# old_motor_line.net
KiCad netlist of a schematic drawn in EAGLE
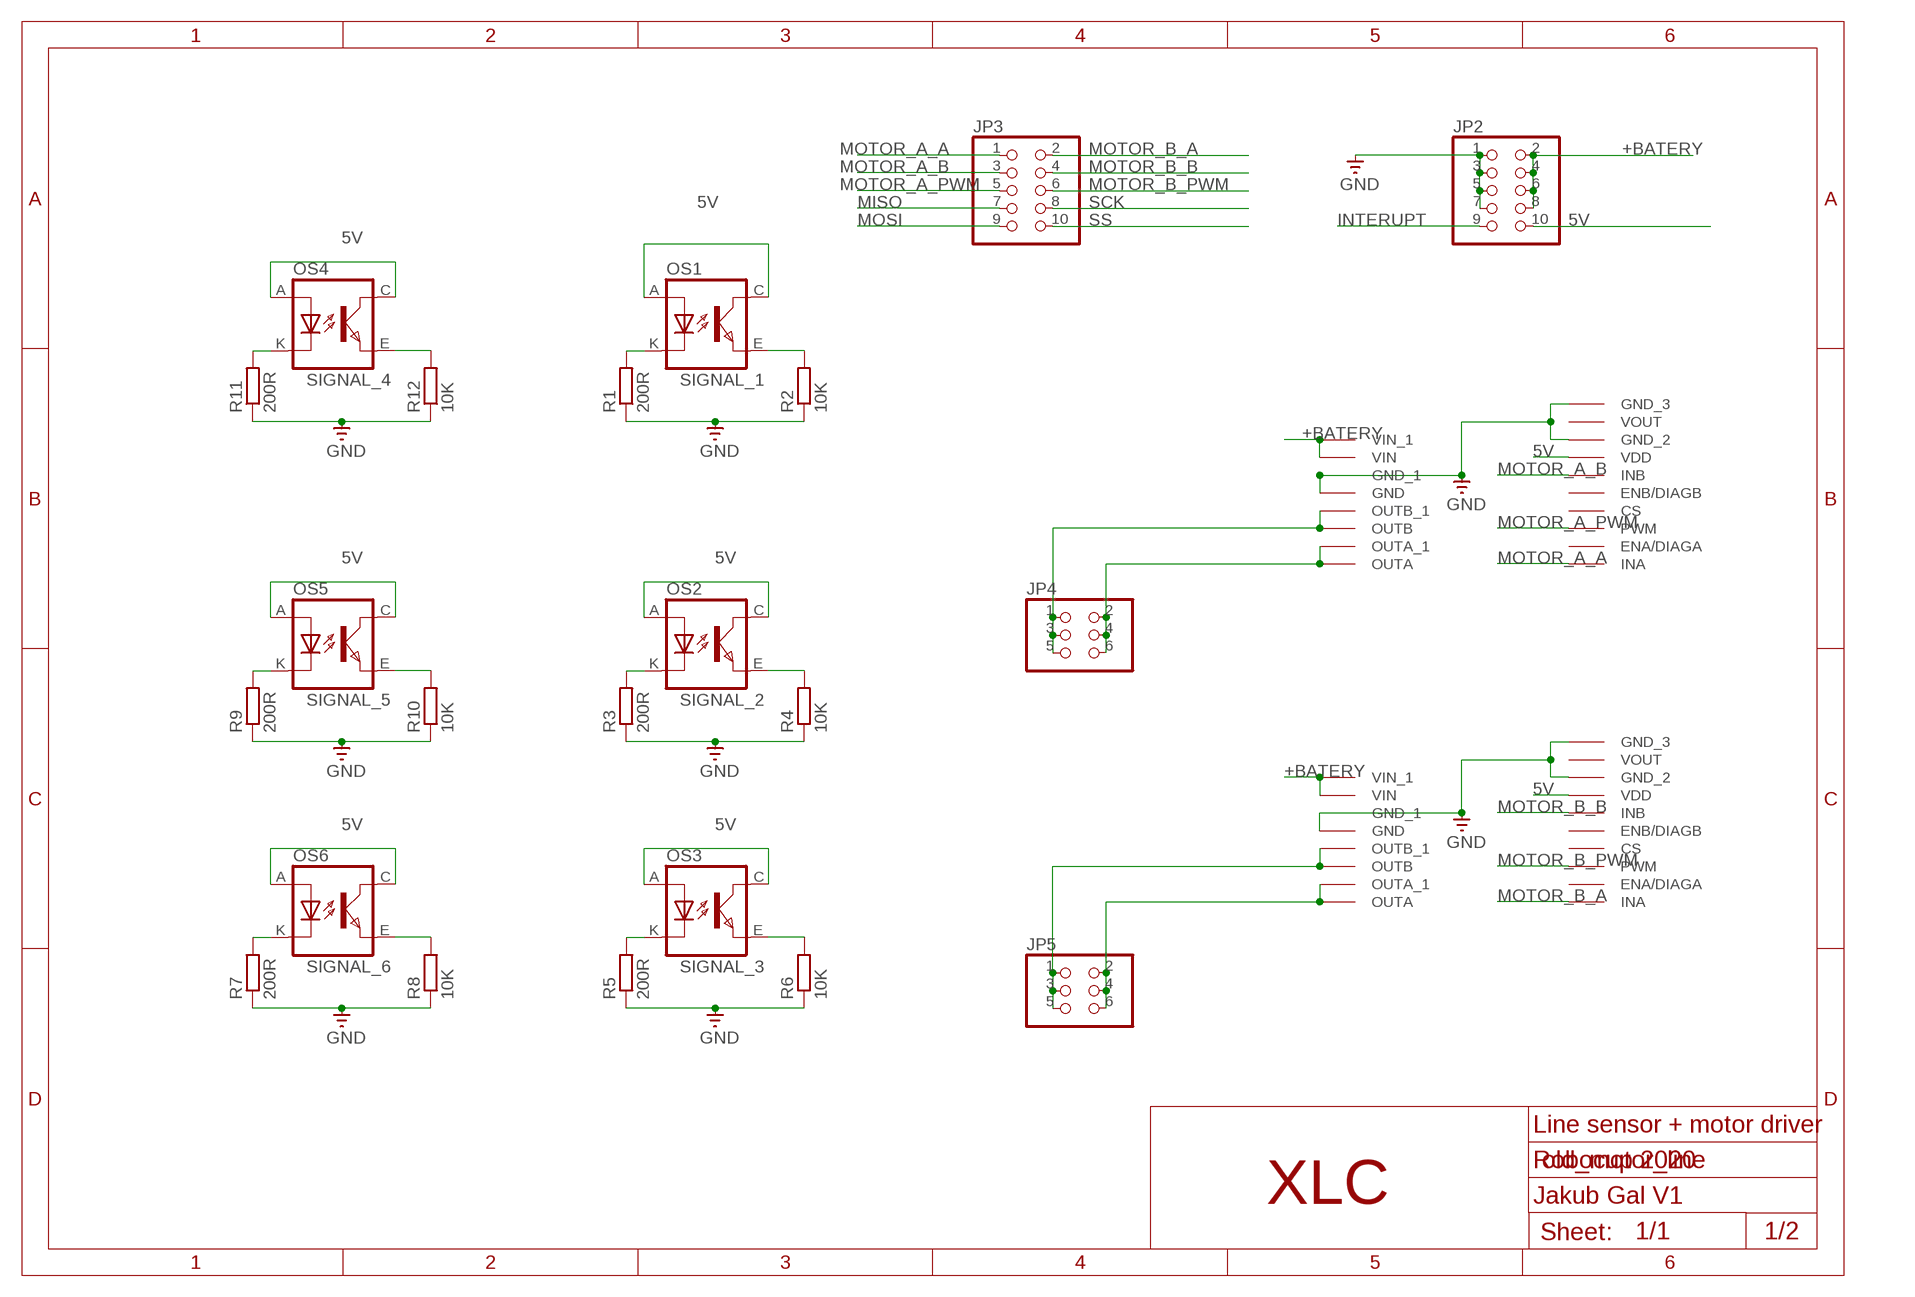
[diagram p0: schematic, sheet 1, part 1 of 2]
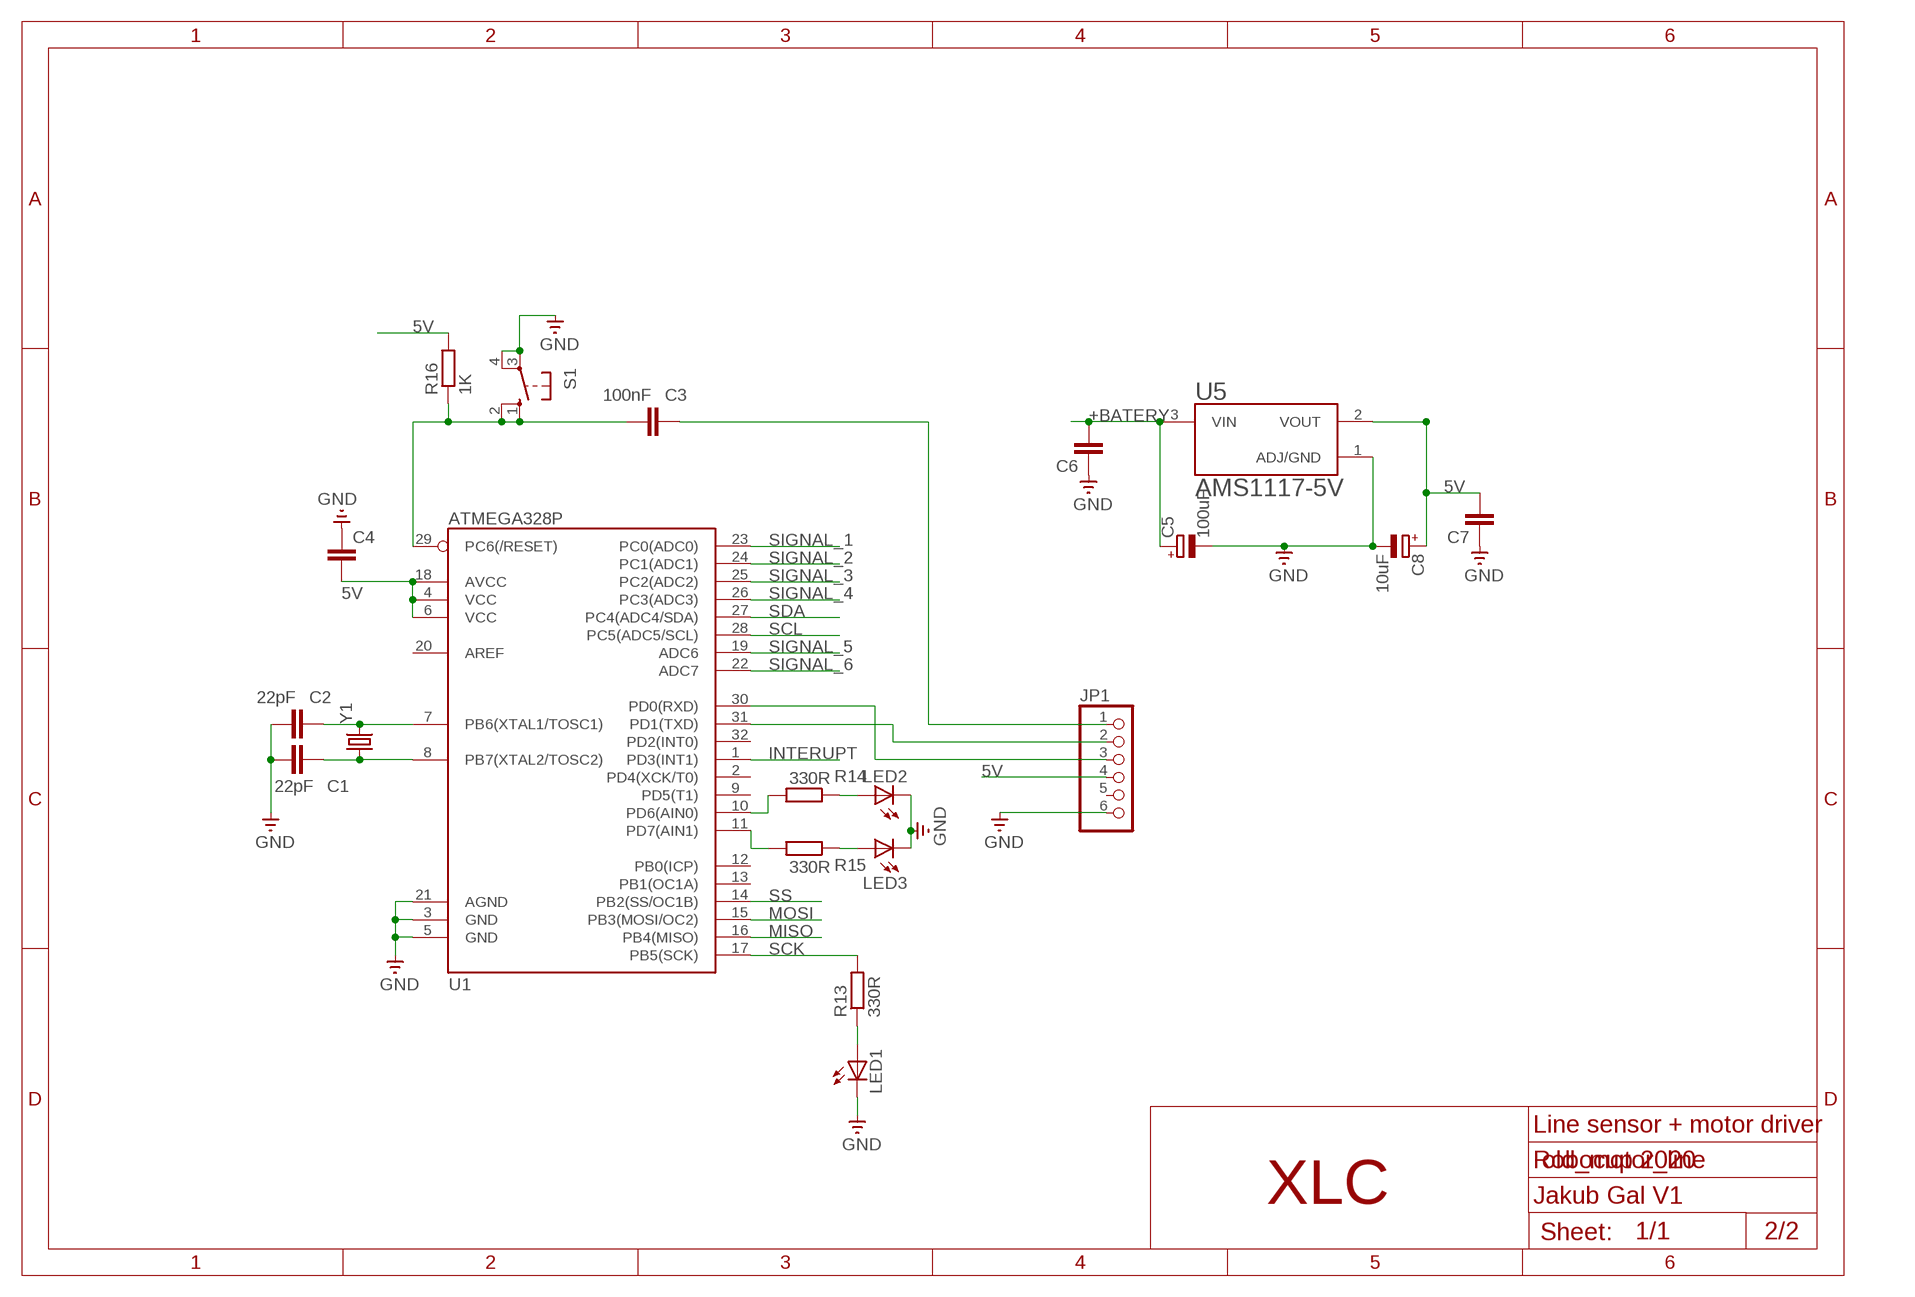
[diagram p1: schematic, sheet 1, part 2 of 2]

(export (version "E")
  (design (tool "Eeschema 10.0.6"))
  (components
    (comp (ref "C1")
      (value "22pF")
      (footprint "eagle-import:C0603")
      (libsource (lib "eagle-import") (part "rcl@1_C-EUC0603"))
    )
    (comp (ref "C2")
      (value "22pF")
      (footprint "eagle-import:C0603")
      (libsource (lib "eagle-import") (part "rcl@1_C-EUC0603"))
    )
    (comp (ref "C3")
      (value "100nF")
      (footprint "eagle-import:C0603")
      (libsource (lib "eagle-import") (part "rcl@1_C-EUC0603"))
    )
    (comp (ref "C4")
      (value "C-EUC0603")
      (footprint "eagle-import:C0603")
      (libsource (lib "eagle-import") (part "C-EUC0603"))
    )
    (comp (ref "C5")
      (value "100uF")
      (footprint "eagle-import:UD-6,3X7,7_NICHICON")
      (libsource (lib "eagle-import") (part "CPOL-EUUD-6,3X7,7"))
    )
    (comp (ref "C6")
      (value "C-EUC0603")
      (footprint "eagle-import:C0603")
      (libsource (lib "eagle-import") (part "C-EUC0603"))
    )
    (comp (ref "C7")
      (value "C-EUC0603")
      (footprint "eagle-import:C0603")
      (libsource (lib "eagle-import") (part "C-EUC0603"))
    )
    (comp (ref "C8")
      (value "10uF")
      (footprint "eagle-import:UD-4X5,8_NICHICON")
      (libsource (lib "eagle-import") (part "CPOL-EUUD-4X5,8"))
    )
    (comp (ref "JP1")
      (value "PINHD-1X6/90")
      (footprint "eagle-import:1X06_90")
      (libsource (lib "eagle-import") (part "PINHD-1X6/90"))
    )
    (comp (ref "JP2")
      (value "PINHD-2X5")
      (footprint "eagle-import:2X05")
      (libsource (lib "eagle-import") (part "PINHD-2X5"))
    )
    (comp (ref "JP3")
      (value "PINHD-2X5")
      (footprint "eagle-import:2X05")
      (libsource (lib "eagle-import") (part "PINHD-2X5"))
    )
    (comp (ref "JP4")
      (value "PINHD-2X3")
      (footprint "eagle-import:2X03")
      (libsource (lib "eagle-import") (part "PINHD-2X3"))
    )
    (comp (ref "JP5")
      (value "PINHD-2X3")
      (footprint "eagle-import:2X03")
      (libsource (lib "eagle-import") (part "PINHD-2X3"))
    )
    (comp (ref "LED1")
      (value "LEDCHIPLED_0603")
      (footprint "eagle-import:CHIPLED_0603")
      (libsource (lib "eagle-import") (part "LEDCHIPLED_0603"))
    )
    (comp (ref "LED2")
      (value "LEDCHIPLED_0603")
      (footprint "eagle-import:CHIPLED_0603")
      (libsource (lib "eagle-import") (part "LEDCHIPLED_0603"))
    )
    (comp (ref "LED3")
      (value "LEDCHIPLED_0603")
      (footprint "eagle-import:CHIPLED_0603")
      (libsource (lib "eagle-import") (part "LEDCHIPLED_0603"))
    )
    (comp (ref "OS1")
      (value "TCRT5000")
      (footprint "eagle-import:TCRT5000")
      (libsource (lib "eagle-import") (part "TCRT5000"))
    )
    (comp (ref "OS2")
      (value "TCRT5000")
      (footprint "eagle-import:TCRT5000")
      (libsource (lib "eagle-import") (part "TCRT5000"))
    )
    (comp (ref "OS3")
      (value "TCRT5000")
      (footprint "eagle-import:TCRT5000")
      (libsource (lib "eagle-import") (part "TCRT5000"))
    )
    (comp (ref "OS4")
      (value "TCRT5000")
      (footprint "eagle-import:TCRT5000")
      (fields (field (name "SPICEPREFIX") "O"))
      (libsource (lib "eagle-import") (part "TCRT5000"))
    )
    (comp (ref "OS5")
      (value "TCRT5000")
      (footprint "eagle-import:TCRT5000")
      (libsource (lib "eagle-import") (part "TCRT5000"))
    )
    (comp (ref "OS6")
      (value "TCRT5000")
      (footprint "eagle-import:TCRT5000")
      (fields (field (name "SPICEPREFIX") "O"))
      (libsource (lib "eagle-import") (part "TCRT5000"))
    )
    (comp (ref "R1")
      (value "200R")
      (footprint "eagle-import:R0603")
      (libsource (lib "eagle-import") (part "R-EU_R0603"))
    )
    (comp (ref "R2")
      (value "10K")
      (footprint "eagle-import:R0603")
      (libsource (lib "eagle-import") (part "R-EU_R0603"))
    )
    (comp (ref "R3")
      (value "200R")
      (footprint "eagle-import:R0603")
      (libsource (lib "eagle-import") (part "R-EU_R0603"))
    )
    (comp (ref "R4")
      (value "10K")
      (footprint "eagle-import:R0603")
      (libsource (lib "eagle-import") (part "R-EU_R0603"))
    )
    (comp (ref "R5")
      (value "200R")
      (footprint "eagle-import:R0603")
      (libsource (lib "eagle-import") (part "R-EU_R0603"))
    )
    (comp (ref "R6")
      (value "10K")
      (footprint "eagle-import:R0603")
      (libsource (lib "eagle-import") (part "R-EU_R0603"))
    )
    (comp (ref "R7")
      (value "200R")
      (footprint "eagle-import:R0603")
      (libsource (lib "eagle-import") (part "R-EU_R0603"))
    )
    (comp (ref "R8")
      (value "10K")
      (footprint "eagle-import:R0603")
      (libsource (lib "eagle-import") (part "R-EU_R0603"))
    )
    (comp (ref "R9")
      (value "200R")
      (footprint "eagle-import:R0603")
      (libsource (lib "eagle-import") (part "R-EU_R0603"))
    )
    (comp (ref "R10")
      (value "10K")
      (footprint "eagle-import:R0603")
      (libsource (lib "eagle-import") (part "R-EU_R0603"))
    )
    (comp (ref "R11")
      (value "200R")
      (footprint "eagle-import:R0603")
      (libsource (lib "eagle-import") (part "R-EU_R0603"))
    )
    (comp (ref "R12")
      (value "10K")
      (footprint "eagle-import:R0603")
      (libsource (lib "eagle-import") (part "R-EU_R0603"))
    )
    (comp (ref "R13")
      (value "330R")
      (footprint "eagle-import:R0603")
      (libsource (lib "eagle-import") (part "R-EU_R0603"))
    )
    (comp (ref "R14")
      (value "330R")
      (footprint "eagle-import:R0603")
      (libsource (lib "eagle-import") (part "R-EU_R0603"))
    )
    (comp (ref "R15")
      (value "330R")
      (footprint "eagle-import:R0603")
      (libsource (lib "eagle-import") (part "R-EU_R0603"))
    )
    (comp (ref "R16")
      (value "1K")
      (footprint "eagle-import:R0603")
      (libsource (lib "eagle-import") (part "R-EU_R0603"))
    )
    (comp (ref "S1")
      (value "10-XX")
      (footprint "eagle-import:B3F-10XX")
      (fields (field (name "MPN") "B3F-1000"))
      (libsource (lib "eagle-import") (part "10-XX"))
    )
    (comp (ref "U$1")
      (value "MOTOR_DRIVER")
      (footprint "eagle-import:MOTOR_DRIVER")
      (libsource (lib "eagle-import") (part "MOTOR_DRIVER"))
    )
    (comp (ref "U$2")
      (value "MOTOR_DRIVER")
      (footprint "eagle-import:MOTOR_DRIVER")
      (libsource (lib "eagle-import") (part "MOTOR_DRIVER"))
    )
    (comp (ref "U1")
      (value "ATMEGA328P")
      (footprint "eagle-import:TQFP32-08")
      (libsource (lib "eagle-import") (part "ATMEGA328_SMT"))
    )
    (comp (ref "U5")
      (value "AMS1117-5V")
      (footprint "eagle-import:SOT229P700X180-4N")
      (fields (field (name "MF") "Advanced Monolithic Systems") (field (name "MP") "AMS1117-3.3"))
      (libsource (lib "eagle-import") (part "AMS1117-3.3"))
    )
    (comp (ref "Y1")
      (value "CRYSTALHC49US")
      (footprint "eagle-import:HC49US")
      (libsource (lib "eagle-import") (part "CRYSTALHC49US"))
    )
  )
  (nets
    (net (code "1") (name "/+BATERY") (class "Default")
      (node (ref "C5") (pin "+") (pinfunction "+_+") (pintype "passive"))
      (node (ref "C6") (pin "2") (pinfunction "2_2") (pintype "passive"))
      (node (ref "JP2") (pin "2") (pinfunction "2_2") (pintype "passive"))
      (node (ref "JP2") (pin "4") (pinfunction "4_4") (pintype "passive"))
      (node (ref "JP2") (pin "6") (pinfunction "6_6") (pintype "passive"))
      (node (ref "JP2") (pin "8") (pinfunction "8_8") (pintype "passive"))
      (node (ref "U$1") (pin "VIN") (pinfunction "VIN_VIN") (pintype "bidirectional"))
      (node (ref "U$1") (pin "VIN_1") (pinfunction "VIN_1_VIN_1") (pintype "bidirectional"))
      (node (ref "U$2") (pin "VIN") (pinfunction "VIN_VIN") (pintype "bidirectional"))
      (node (ref "U$2") (pin "VIN_1") (pinfunction "VIN_1_VIN_1") (pintype "bidirectional"))
      (node (ref "U5") (pin "3") (pinfunction "VIN_3") (pintype "input"))
    )
    (net (code "2") (name "/5V") (class "Default")
      (node (ref "C4") (pin "2") (pinfunction "2_2") (pintype "passive"))
      (node (ref "C7") (pin "2") (pinfunction "2_2") (pintype "passive"))
      (node (ref "C8") (pin "+") (pinfunction "+_+") (pintype "passive"))
      (node (ref "JP1") (pin "4") (pinfunction "4_4") (pintype "passive"))
      (node (ref "JP2") (pin "10") (pinfunction "10_10") (pintype "passive"))
      (node (ref "OS1") (pin "A") (pinfunction "ANODE_A") (pintype "passive"))
      (node (ref "OS1") (pin "C") (pinfunction "COLLECTOR_C") (pintype "passive"))
      (node (ref "OS2") (pin "A") (pinfunction "ANODE_A") (pintype "passive"))
      (node (ref "OS2") (pin "C") (pinfunction "COLLECTOR_C") (pintype "passive"))
      (node (ref "OS3") (pin "A") (pinfunction "ANODE_A") (pintype "passive"))
      (node (ref "OS3") (pin "C") (pinfunction "COLLECTOR_C") (pintype "passive"))
      (node (ref "OS4") (pin "A") (pinfunction "ANODE_A") (pintype "passive"))
      (node (ref "OS4") (pin "C") (pinfunction "COLLECTOR_C") (pintype "passive"))
      (node (ref "OS5") (pin "A") (pinfunction "ANODE_A") (pintype "passive"))
      (node (ref "OS5") (pin "C") (pinfunction "COLLECTOR_C") (pintype "passive"))
      (node (ref "OS6") (pin "A") (pinfunction "ANODE_A") (pintype "passive"))
      (node (ref "OS6") (pin "C") (pinfunction "COLLECTOR_C") (pintype "passive"))
      (node (ref "R16") (pin "2") (pinfunction "2_2") (pintype "passive"))
      (node (ref "U$1") (pin "VDD") (pinfunction "VDD_VDD") (pintype "bidirectional"))
      (node (ref "U$2") (pin "VDD") (pinfunction "VDD_VDD") (pintype "bidirectional"))
      (node (ref "U1") (pin "18") (pinfunction "AVCC_18") (pintype "bidirectional"))
      (node (ref "U1") (pin "4") (pinfunction "VCC_4") (pintype "bidirectional"))
      (node (ref "U1") (pin "6") (pinfunction "VCC_6") (pintype "bidirectional"))
      (node (ref "U5") (pin "2") (pinfunction "VOUT_2") (pintype "output"))
    )
    (net (code "3") (name "/INTERUPT") (class "Default")
      (node (ref "JP2") (pin "9") (pinfunction "9_9") (pintype "passive"))
      (node (ref "U1") (pin "1") (pinfunction "PD3(INT1)_1") (pintype "bidirectional"))
    )
    (net (code "4") (name "/MISO") (class "Default")
      (node (ref "JP3") (pin "7") (pinfunction "7_7") (pintype "passive"))
      (node (ref "U1") (pin "16") (pinfunction "PB4(MISO)_16") (pintype "bidirectional"))
    )
    (net (code "5") (name "/MOSI") (class "Default")
      (node (ref "JP3") (pin "9") (pinfunction "9_9") (pintype "passive"))
      (node (ref "U1") (pin "15") (pinfunction "PB3(MOSI/OC2)_15") (pintype "bidirectional"))
    )
    (net (code "6") (name "/MOTOR_A_A") (class "Default")
      (node (ref "JP3") (pin "1") (pinfunction "1_1") (pintype "passive"))
      (node (ref "U$1") (pin "INA") (pinfunction "INA_INA") (pintype "bidirectional"))
    )
    (net (code "7") (name "/MOTOR_A_B") (class "Default")
      (node (ref "JP3") (pin "3") (pinfunction "3_3") (pintype "passive"))
      (node (ref "U$1") (pin "INB") (pinfunction "INB_INB") (pintype "bidirectional"))
    )
    (net (code "8") (name "/MOTOR_A_PWM") (class "Default")
      (node (ref "JP3") (pin "5") (pinfunction "5_5") (pintype "passive"))
      (node (ref "U$1") (pin "PWM") (pinfunction "PWM_PWM") (pintype "bidirectional"))
    )
    (net (code "9") (name "/MOTOR_B_A") (class "Default")
      (node (ref "JP3") (pin "2") (pinfunction "2_2") (pintype "passive"))
      (node (ref "U$2") (pin "INA") (pinfunction "INA_INA") (pintype "bidirectional"))
    )
    (net (code "10") (name "/MOTOR_B_B") (class "Default")
      (node (ref "JP3") (pin "4") (pinfunction "4_4") (pintype "passive"))
      (node (ref "U$2") (pin "INB") (pinfunction "INB_INB") (pintype "bidirectional"))
    )
    (net (code "11") (name "/MOTOR_B_PWM") (class "Default")
      (node (ref "JP3") (pin "6") (pinfunction "6_6") (pintype "passive"))
      (node (ref "U$2") (pin "PWM") (pinfunction "PWM_PWM") (pintype "bidirectional"))
    )
    (net (code "12") (name "/SCK") (class "Default")
      (node (ref "JP3") (pin "8") (pinfunction "8_8") (pintype "passive"))
      (node (ref "R13") (pin "2") (pinfunction "2_2") (pintype "passive"))
      (node (ref "U1") (pin "17") (pinfunction "PB5(SCK)_17") (pintype "bidirectional"))
    )
    (net (code "13") (name "/SCL") (class "Default")
      (node (ref "U1") (pin "28") (pinfunction "PC5(ADC5/SCL)_28") (pintype "bidirectional"))
    )
    (net (code "14") (name "/SDA") (class "Default")
      (node (ref "U1") (pin "27") (pinfunction "PC4(ADC4/SDA)_27") (pintype "bidirectional"))
    )
    (net (code "15") (name "/SIGNAL_1") (class "Default")
      (node (ref "OS1") (pin "E") (pinfunction "EMITTER_E") (pintype "passive"))
      (node (ref "R2") (pin "2") (pinfunction "2_2") (pintype "passive"))
      (node (ref "U1") (pin "23") (pinfunction "PC0(ADC0)_23") (pintype "bidirectional"))
    )
    (net (code "16") (name "/SIGNAL_2") (class "Default")
      (node (ref "OS2") (pin "E") (pinfunction "EMITTER_E") (pintype "passive"))
      (node (ref "R4") (pin "2") (pinfunction "2_2") (pintype "passive"))
      (node (ref "U1") (pin "24") (pinfunction "PC1(ADC1)_24") (pintype "bidirectional"))
    )
    (net (code "17") (name "/SIGNAL_3") (class "Default")
      (node (ref "OS3") (pin "E") (pinfunction "EMITTER_E") (pintype "passive"))
      (node (ref "R6") (pin "2") (pinfunction "2_2") (pintype "passive"))
      (node (ref "U1") (pin "25") (pinfunction "PC2(ADC2)_25") (pintype "bidirectional"))
    )
    (net (code "18") (name "/SIGNAL_4") (class "Default")
      (node (ref "OS4") (pin "E") (pinfunction "EMITTER_E") (pintype "passive"))
      (node (ref "R12") (pin "2") (pinfunction "2_2") (pintype "passive"))
      (node (ref "U1") (pin "26") (pinfunction "PC3(ADC3)_26") (pintype "bidirectional"))
    )
    (net (code "19") (name "/SIGNAL_5") (class "Default")
      (node (ref "OS5") (pin "E") (pinfunction "EMITTER_E") (pintype "passive"))
      (node (ref "R10") (pin "2") (pinfunction "2_2") (pintype "passive"))
      (node (ref "U1") (pin "19") (pinfunction "ADC6_19") (pintype "bidirectional"))
    )
    (net (code "20") (name "/SIGNAL_6") (class "Default")
      (node (ref "OS6") (pin "E") (pinfunction "EMITTER_E") (pintype "passive"))
      (node (ref "R8") (pin "2") (pinfunction "2_2") (pintype "passive"))
      (node (ref "U1") (pin "22") (pinfunction "ADC7_22") (pintype "bidirectional"))
    )
    (net (code "21") (name "/SS") (class "Default")
      (node (ref "JP3") (pin "10") (pinfunction "10_10") (pintype "passive"))
      (node (ref "U1") (pin "14") (pinfunction "PB2(SS/OC1B)_14") (pintype "bidirectional"))
    )
    (net (code "22") (name "GND") (class "Default")
      (node (ref "C1") (pin "1") (pinfunction "1_1") (pintype "passive"))
      (node (ref "C2") (pin "1") (pinfunction "1_1") (pintype "passive"))
      (node (ref "C4") (pin "1") (pinfunction "1_1") (pintype "passive"))
      (node (ref "C5") (pin "-") (pinfunction "-_-") (pintype "passive"))
      (node (ref "C6") (pin "1") (pinfunction "1_1") (pintype "passive"))
      (node (ref "C7") (pin "1") (pinfunction "1_1") (pintype "passive"))
      (node (ref "C8") (pin "-") (pinfunction "-_-") (pintype "passive"))
      (node (ref "JP1") (pin "6") (pinfunction "6_6") (pintype "passive"))
      (node (ref "JP2") (pin "1") (pinfunction "1_1") (pintype "passive"))
      (node (ref "JP2") (pin "3") (pinfunction "3_3") (pintype "passive"))
      (node (ref "JP2") (pin "5") (pinfunction "5_5") (pintype "passive"))
      (node (ref "JP2") (pin "7") (pinfunction "7_7") (pintype "passive"))
      (node (ref "LED1") (pin "C") (pinfunction "C_C") (pintype "passive"))
      (node (ref "LED2") (pin "C") (pinfunction "C_C") (pintype "passive"))
      (node (ref "LED3") (pin "C") (pinfunction "C_C") (pintype "passive"))
      (node (ref "R1") (pin "1") (pinfunction "1_1") (pintype "passive"))
      (node (ref "R10") (pin "1") (pinfunction "1_1") (pintype "passive"))
      (node (ref "R11") (pin "1") (pinfunction "1_1") (pintype "passive"))
      (node (ref "R12") (pin "1") (pinfunction "1_1") (pintype "passive"))
      (node (ref "R2") (pin "1") (pinfunction "1_1") (pintype "passive"))
      (node (ref "R3") (pin "1") (pinfunction "1_1") (pintype "passive"))
      (node (ref "R4") (pin "1") (pinfunction "1_1") (pintype "passive"))
      (node (ref "R5") (pin "1") (pinfunction "1_1") (pintype "passive"))
      (node (ref "R6") (pin "1") (pinfunction "1_1") (pintype "passive"))
      (node (ref "R7") (pin "1") (pinfunction "1_1") (pintype "passive"))
      (node (ref "R8") (pin "1") (pinfunction "1_1") (pintype "passive"))
      (node (ref "R9") (pin "1") (pinfunction "1_1") (pintype "passive"))
      (node (ref "S1") (pin "3") (pinfunction "P_3") (pintype "passive"))
      (node (ref "S1") (pin "4") (pinfunction "P1_4") (pintype "passive"))
      (node (ref "U$1") (pin "GND") (pinfunction "GND_GND") (pintype "bidirectional"))
      (node (ref "U$1") (pin "GND_1") (pinfunction "GND_1_GND_1") (pintype "bidirectional"))
      (node (ref "U$1") (pin "GND_2") (pinfunction "GND_2_GND_2") (pintype "bidirectional"))
      (node (ref "U$1") (pin "GND_3") (pinfunction "GND_3_GND_3") (pintype "bidirectional"))
      (node (ref "U$2") (pin "GND") (pinfunction "GND_GND") (pintype "bidirectional"))
      (node (ref "U$2") (pin "GND_1") (pinfunction "GND_1_GND_1") (pintype "bidirectional"))
      (node (ref "U$2") (pin "GND_2") (pinfunction "GND_2_GND_2") (pintype "bidirectional"))
      (node (ref "U$2") (pin "GND_3") (pinfunction "GND_3_GND_3") (pintype "bidirectional"))
      (node (ref "U1") (pin "21") (pinfunction "AGND_21") (pintype "bidirectional"))
      (node (ref "U1") (pin "3") (pinfunction "GND_3") (pintype "bidirectional"))
      (node (ref "U1") (pin "5") (pinfunction "GND_5") (pintype "bidirectional"))
      (node (ref "U5") (pin "1") (pinfunction "ADJ/GND_1") (pintype "power_in"))
    )
    (net (code "23") (name "Net-(C3-Pad2)") (class "Default")
      (node (ref "C3") (pin "2") (pinfunction "2_2") (pintype "passive"))
      (node (ref "JP1") (pin "1") (pinfunction "1_1") (pintype "passive"))
    )
    (net (code "24") (name "Net-(JP4-Pad1)") (class "Default")
      (node (ref "JP4") (pin "1") (pinfunction "1_1") (pintype "passive"))
      (node (ref "JP4") (pin "3") (pinfunction "3_3") (pintype "passive"))
      (node (ref "JP4") (pin "5") (pinfunction "5_5") (pintype "passive"))
      (node (ref "U$1") (pin "OUTB") (pinfunction "OUTB_OUTB") (pintype "bidirectional"))
      (node (ref "U$1") (pin "OUTB_1") (pinfunction "OUTB_1_OUTB_1") (pintype "bidirectional"))
    )
    (net (code "25") (name "Net-(JP4-Pad2)") (class "Default")
      (node (ref "JP4") (pin "2") (pinfunction "2_2") (pintype "passive"))
      (node (ref "JP4") (pin "4") (pinfunction "4_4") (pintype "passive"))
      (node (ref "JP4") (pin "6") (pinfunction "6_6") (pintype "passive"))
      (node (ref "U$1") (pin "OUTA") (pinfunction "OUTA_OUTA") (pintype "bidirectional"))
      (node (ref "U$1") (pin "OUTA_1") (pinfunction "OUTA_1_OUTA_1") (pintype "bidirectional"))
    )
    (net (code "26") (name "Net-(JP5-Pad1)") (class "Default")
      (node (ref "JP5") (pin "1") (pinfunction "1_1") (pintype "passive"))
      (node (ref "JP5") (pin "3") (pinfunction "3_3") (pintype "passive"))
      (node (ref "JP5") (pin "5") (pinfunction "5_5") (pintype "passive"))
      (node (ref "U$2") (pin "OUTB") (pinfunction "OUTB_OUTB") (pintype "bidirectional"))
      (node (ref "U$2") (pin "OUTB_1") (pinfunction "OUTB_1_OUTB_1") (pintype "bidirectional"))
    )
    (net (code "27") (name "Net-(JP5-Pad2)") (class "Default")
      (node (ref "JP5") (pin "2") (pinfunction "2_2") (pintype "passive"))
      (node (ref "JP5") (pin "4") (pinfunction "4_4") (pintype "passive"))
      (node (ref "JP5") (pin "6") (pinfunction "6_6") (pintype "passive"))
      (node (ref "U$2") (pin "OUTA") (pinfunction "OUTA_OUTA") (pintype "bidirectional"))
      (node (ref "U$2") (pin "OUTA_1") (pinfunction "OUTA_1_OUTA_1") (pintype "bidirectional"))
    )
    (net (code "28") (name "Net-(LED1-PadA)") (class "Default")
      (node (ref "LED1") (pin "A") (pinfunction "A_A") (pintype "passive"))
      (node (ref "R13") (pin "1") (pinfunction "1_1") (pintype "passive"))
    )
    (net (code "29") (name "Net-(LED2-PadA)") (class "Default")
      (node (ref "LED2") (pin "A") (pinfunction "A_A") (pintype "passive"))
      (node (ref "R14") (pin "1") (pinfunction "1_1") (pintype "passive"))
    )
    (net (code "30") (name "Net-(LED3-PadA)") (class "Default")
      (node (ref "LED3") (pin "A") (pinfunction "A_A") (pintype "passive"))
      (node (ref "R15") (pin "1") (pinfunction "1_1") (pintype "passive"))
    )
    (net (code "31") (name "Net-(OS1-CATHODE)") (class "Default")
      (node (ref "OS1") (pin "K") (pinfunction "CATHODE_K") (pintype "passive"))
      (node (ref "R1") (pin "2") (pinfunction "2_2") (pintype "passive"))
    )
    (net (code "32") (name "Net-(OS2-CATHODE)") (class "Default")
      (node (ref "OS2") (pin "K") (pinfunction "CATHODE_K") (pintype "passive"))
      (node (ref "R3") (pin "2") (pinfunction "2_2") (pintype "passive"))
    )
    (net (code "33") (name "Net-(OS3-CATHODE)") (class "Default")
      (node (ref "OS3") (pin "K") (pinfunction "CATHODE_K") (pintype "passive"))
      (node (ref "R5") (pin "2") (pinfunction "2_2") (pintype "passive"))
    )
    (net (code "34") (name "Net-(OS4-CATHODE)") (class "Default")
      (node (ref "OS4") (pin "K") (pinfunction "CATHODE_K") (pintype "passive"))
      (node (ref "R11") (pin "2") (pinfunction "2_2") (pintype "passive"))
    )
    (net (code "35") (name "Net-(OS5-CATHODE)") (class "Default")
      (node (ref "OS5") (pin "K") (pinfunction "CATHODE_K") (pintype "passive"))
      (node (ref "R9") (pin "2") (pinfunction "2_2") (pintype "passive"))
    )
    (net (code "36") (name "Net-(OS6-CATHODE)") (class "Default")
      (node (ref "OS6") (pin "K") (pinfunction "CATHODE_K") (pintype "passive"))
      (node (ref "R7") (pin "2") (pinfunction "2_2") (pintype "passive"))
    )
    (net (code "37") (name "Net-(S1-S)") (class "Default")
      (node (ref "C3") (pin "1") (pinfunction "1_1") (pintype "passive"))
      (node (ref "R16") (pin "1") (pinfunction "1_1") (pintype "passive"))
      (node (ref "S1") (pin "1") (pinfunction "S_1") (pintype "passive"))
      (node (ref "S1") (pin "2") (pinfunction "S1_2") (pintype "passive"))
      (node (ref "U1") (pin "29") (pinfunction "PC6(/RESET)_29") (pintype "bidirectional"))
    )
    (net (code "38") (name "Net-(U1-PB6(XTAL1{slash}TOSC1))") (class "Default")
      (node (ref "C2") (pin "2") (pinfunction "2_2") (pintype "passive"))
      (node (ref "U1") (pin "7") (pinfunction "PB6(XTAL1/TOSC1)_7") (pintype "bidirectional"))
      (node (ref "Y1") (pin "2") (pinfunction "2_2") (pintype "passive"))
    )
    (net (code "39") (name "Net-(U1-PB7(XTAL2{slash}TOSC2))") (class "Default")
      (node (ref "C1") (pin "2") (pinfunction "2_2") (pintype "passive"))
      (node (ref "U1") (pin "8") (pinfunction "PB7(XTAL2/TOSC2)_8") (pintype "bidirectional"))
      (node (ref "Y1") (pin "1") (pinfunction "1_1") (pintype "passive"))
    )
    (net (code "40") (name "Net-(U1-PD0(RXD))") (class "Default")
      (node (ref "JP1") (pin "3") (pinfunction "3_3") (pintype "passive"))
      (node (ref "U1") (pin "30") (pinfunction "PD0(RXD)_30") (pintype "bidirectional"))
    )
    (net (code "41") (name "Net-(U1-PD1(TXD))") (class "Default")
      (node (ref "JP1") (pin "2") (pinfunction "2_2") (pintype "passive"))
      (node (ref "U1") (pin "31") (pinfunction "PD1(TXD)_31") (pintype "bidirectional"))
    )
    (net (code "42") (name "Net-(U1-PD6(AIN0))") (class "Default")
      (node (ref "R14") (pin "2") (pinfunction "2_2") (pintype "passive"))
      (node (ref "U1") (pin "10") (pinfunction "PD6(AIN0)_10") (pintype "bidirectional"))
    )
    (net (code "43") (name "Net-(U1-PD7(AIN1))") (class "Default")
      (node (ref "R15") (pin "2") (pinfunction "2_2") (pintype "passive"))
      (node (ref "U1") (pin "11") (pinfunction "PD7(AIN1)_11") (pintype "bidirectional"))
    )
    (net (code "44") (name "unconnected-(JP1-Pad5)") (class "Default")
      (node (ref "JP1") (pin "5") (pinfunction "5_5") (pintype "passive"))
    )
    (net (code "45") (name "unconnected-(U$1-PadCS)") (class "Default")
      (node (ref "U$1") (pin "CS") (pinfunction "CS_CS") (pintype "bidirectional"))
    )
    (net (code "46") (name "unconnected-(U$1-PadENA{slash}DIAGA)") (class "Default")
      (node (ref "U$1") (pin "ENA/DIAGA") (pinfunction "ENA/DIAGA_ENA/DIAGA") (pintype "bidirectional"))
    )
    (net (code "47") (name "unconnected-(U$1-PadENB{slash}DIAGB)") (class "Default")
      (node (ref "U$1") (pin "ENB/DIAGB") (pinfunction "ENB/DIAGB_ENB/DIAGB") (pintype "bidirectional"))
    )
    (net (code "48") (name "unconnected-(U$1-PadVOUT)") (class "Default")
      (node (ref "U$1") (pin "VOUT") (pinfunction "VOUT_VOUT") (pintype "bidirectional"))
    )
    (net (code "49") (name "unconnected-(U$2-PadCS)") (class "Default")
      (node (ref "U$2") (pin "CS") (pinfunction "CS_CS") (pintype "bidirectional"))
    )
    (net (code "50") (name "unconnected-(U$2-PadENA{slash}DIAGA)") (class "Default")
      (node (ref "U$2") (pin "ENA/DIAGA") (pinfunction "ENA/DIAGA_ENA/DIAGA") (pintype "bidirectional"))
    )
    (net (code "51") (name "unconnected-(U$2-PadENB{slash}DIAGB)") (class "Default")
      (node (ref "U$2") (pin "ENB/DIAGB") (pinfunction "ENB/DIAGB_ENB/DIAGB") (pintype "bidirectional"))
    )
    (net (code "52") (name "unconnected-(U$2-PadVOUT)") (class "Default")
      (node (ref "U$2") (pin "VOUT") (pinfunction "VOUT_VOUT") (pintype "bidirectional"))
    )
    (net (code "53") (name "unconnected-(U1-AREF-Pad20)") (class "Default")
      (node (ref "U1") (pin "20") (pinfunction "AREF_20") (pintype "bidirectional"))
    )
    (net (code "54") (name "unconnected-(U1-PB0(ICP)-Pad12)") (class "Default")
      (node (ref "U1") (pin "12") (pinfunction "PB0(ICP)_12") (pintype "bidirectional"))
    )
    (net (code "55") (name "unconnected-(U1-PB1(OC1A)-Pad13)") (class "Default")
      (node (ref "U1") (pin "13") (pinfunction "PB1(OC1A)_13") (pintype "bidirectional"))
    )
    (net (code "56") (name "unconnected-(U1-PD2(INT0)-Pad32)") (class "Default")
      (node (ref "U1") (pin "32") (pinfunction "PD2(INT0)_32") (pintype "bidirectional"))
    )
    (net (code "57") (name "unconnected-(U1-PD4(XCK{slash}T0)-Pad2)") (class "Default")
      (node (ref "U1") (pin "2") (pinfunction "PD4(XCK/T0)_2") (pintype "bidirectional"))
    )
    (net (code "58") (name "unconnected-(U1-PD5(T1)-Pad9)") (class "Default")
      (node (ref "U1") (pin "9") (pinfunction "PD5(T1)_9") (pintype "bidirectional"))
    )
  )
)
